# SINTETIZADOR_Y_DDS_SLAVE.net
KiCad netlist of a schematic drawn in Altium Designer
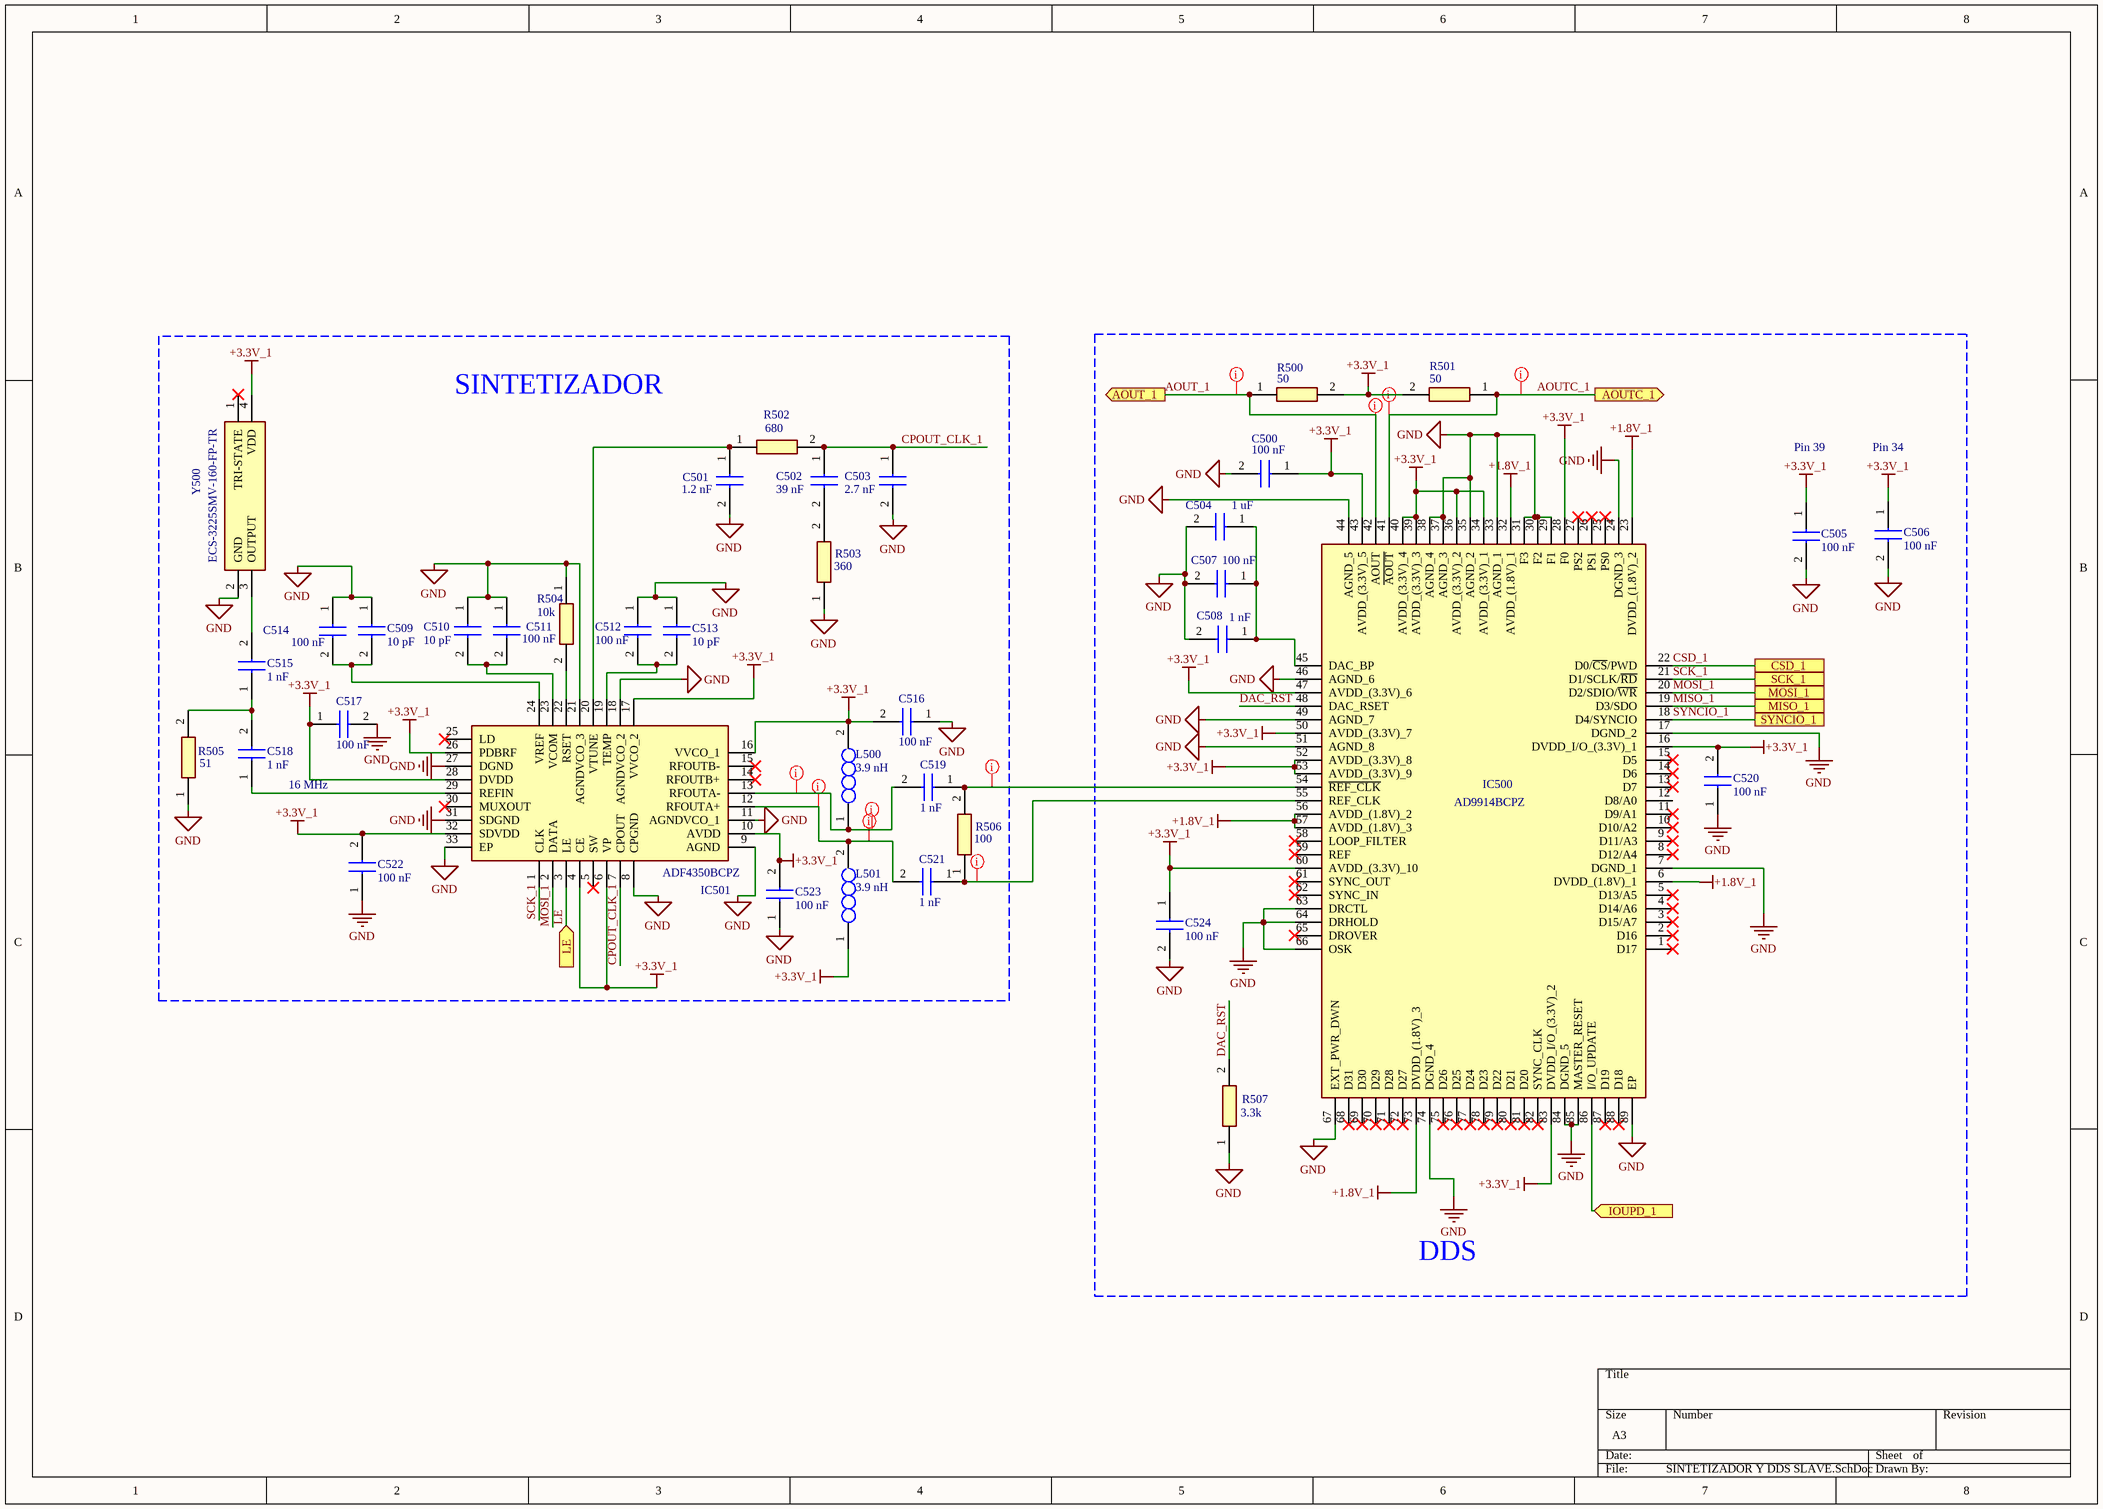
[diagram p0: SINTETIZADOR Y DDS SLAVE.SchDoc]

(export (version "E")
  (design (tool "Eeschema 10.0.6"))
  (components
    (comp (ref "C500")
      (value "100 nF")
      (footprint "SamacSys:C0603")
      (description "Capacitor")
      (fields (field (name "MANUFACTURER_PART_NUMBER") "C0603H470J5GACTU"))
      (libsource (lib "LIBRERIA_GEN_V2.0") (part "C0603H470J5GACTU"))
    )
    (comp (ref "C501")
      (value "1.2 nF")
      (footprint "SamacSys:C0603")
      (description "Capacitor")
      (fields (field (name "MANUFACTURER_PART_NUMBER") "C0603H470J5GACTU"))
      (libsource (lib "LIBRERIA_GEN_V2.0") (part "C0603H470J5GACTU"))
    )
    (comp (ref "C502")
      (value "39 nF")
      (footprint "SamacSys:C0603")
      (description "Capacitor")
      (fields (field (name "MANUFACTURER_PART_NUMBER") "C0603H470J5GACTU"))
      (libsource (lib "LIBRERIA_GEN_V2.0") (part "C0603H470J5GACTU"))
    )
    (comp (ref "C503")
      (value "2.7 nF")
      (footprint "SamacSys:C0603")
      (description "Capacitor")
      (fields (field (name "MANUFACTURER_PART_NUMBER") "C0603H470J5GACTU"))
      (libsource (lib "LIBRERIA_GEN_V2.0") (part "C0603H470J5GACTU"))
    )
    (comp (ref "C504")
      (value "1 uF")
      (footprint "SamacSys:C0603")
      (description "Capacitor")
      (fields (field (name "MANUFACTURER_PART_NUMBER") "C0603H470J5GACTU"))
      (libsource (lib "LIBRERIA_GEN_V2.0") (part "C0603H470J5GACTU"))
    )
    (comp (ref "C505")
      (value "100 nF")
      (footprint "SamacSys:C0603")
      (description "Capacitor")
      (fields (field (name "MANUFACTURER_PART_NUMBER") "C0603H470J5GACTU"))
      (libsource (lib "LIBRERIA_GEN_V2.0") (part "C0603H470J5GACTU"))
    )
    (comp (ref "C506")
      (value "100 nF")
      (footprint "SamacSys:C0603")
      (description "Capacitor")
      (fields (field (name "MANUFACTURER_PART_NUMBER") "C0603H470J5GACTU"))
      (libsource (lib "LIBRERIA_GEN_V2.0") (part "C0603H470J5GACTU"))
    )
    (comp (ref "C507")
      (value "100 nF")
      (footprint "SamacSys:C0603")
      (description "Capacitor")
      (fields (field (name "MANUFACTURER_PART_NUMBER") "C0603H470J5GACTU"))
      (libsource (lib "LIBRERIA_GEN_V2.0") (part "C0603H470J5GACTU"))
    )
    (comp (ref "C508")
      (value "1 nF")
      (footprint "SamacSys:C0603")
      (description "Capacitor")
      (fields (field (name "MANUFACTURER_PART_NUMBER") "C0603H470J5GACTU"))
      (libsource (lib "LIBRERIA_GEN_V2.0") (part "C0603H470J5GACTU"))
    )
    (comp (ref "C509")
      (value "10 pF")
      (footprint "SamacSys:C0603")
      (description "Capacitor")
      (fields (field (name "MANUFACTURER_PART_NUMBER") "C0603H470J5GACTU"))
      (libsource (lib "LIBRERIA_GEN_V2.0") (part "C0603H470J5GACTU"))
    )
    (comp (ref "C510")
      (value "10 pF")
      (footprint "SamacSys:C0603")
      (description "Capacitor")
      (fields (field (name "MANUFACTURER_PART_NUMBER") "C0603H470J5GACTU"))
      (libsource (lib "LIBRERIA_GEN_V2.0") (part "C0603H470J5GACTU"))
    )
    (comp (ref "C511")
      (value "100 nF")
      (footprint "SamacSys:C0603")
      (description "Capacitor")
      (fields (field (name "MANUFACTURER_PART_NUMBER") "C0603H470J5GACTU"))
      (libsource (lib "LIBRERIA_GEN_V2.0") (part "C0603H470J5GACTU"))
    )
    (comp (ref "C512")
      (value "100 nF")
      (footprint "SamacSys:C0603")
      (description "Capacitor")
      (fields (field (name "MANUFACTURER_PART_NUMBER") "C0603H470J5GACTU"))
      (libsource (lib "LIBRERIA_GEN_V2.0") (part "C0603H470J5GACTU"))
    )
    (comp (ref "C513")
      (value "10 pF")
      (footprint "SamacSys:C0603")
      (description "Capacitor")
      (fields (field (name "MANUFACTURER_PART_NUMBER") "C0603H470J5GACTU"))
      (libsource (lib "LIBRERIA_GEN_V2.0") (part "C0603H470J5GACTU"))
    )
    (comp (ref "C514")
      (value "100 nF")
      (footprint "SamacSys:C0603")
      (description "Capacitor")
      (fields (field (name "MANUFACTURER_PART_NUMBER") "C0603H470J5GACTU"))
      (libsource (lib "LIBRERIA_GEN_V2.0") (part "C0603H470J5GACTU"))
    )
    (comp (ref "C515")
      (value "1 nF")
      (footprint "SamacSys:C0603")
      (description "Capacitor")
      (fields (field (name "MANUFACTURER_PART_NUMBER") "C0603H470J5GACTU"))
      (libsource (lib "LIBRERIA_GEN_V2.0") (part "C0603H470J5GACTU"))
    )
    (comp (ref "C516")
      (value "100 nF")
      (footprint "SamacSys:C0603")
      (description "Capacitor")
      (fields (field (name "MANUFACTURER_PART_NUMBER") "C0603H470J5GACTU"))
      (libsource (lib "LIBRERIA_GEN_V2.0") (part "C0603H470J5GACTU"))
    )
    (comp (ref "C517")
      (value "100 nF")
      (footprint "SamacSys:C0603")
      (description "Capacitor")
      (fields (field (name "MANUFACTURER_PART_NUMBER") "C0603H470J5GACTU"))
      (libsource (lib "LIBRERIA_GEN_V2.0") (part "C0603H470J5GACTU"))
    )
    (comp (ref "C518")
      (value "1 nF")
      (footprint "SamacSys:C0603")
      (description "Capacitor")
      (fields (field (name "MANUFACTURER_PART_NUMBER") "C0603H470J5GACTU"))
      (libsource (lib "LIBRERIA_GEN_V2.0") (part "C0603H470J5GACTU"))
    )
    (comp (ref "C519")
      (value "1 nF")
      (footprint "SamacSys:C0603")
      (description "Capacitor")
      (fields (field (name "MANUFACTURER_PART_NUMBER") "C0603H470J5GACTU"))
      (libsource (lib "LIBRERIA_GEN_V2.0") (part "C0603H470J5GACTU"))
    )
    (comp (ref "C520")
      (value "100 nF")
      (footprint "SamacSys:C0603")
      (description "Capacitor")
      (fields (field (name "MANUFACTURER_PART_NUMBER") "C0603H470J5GACTU"))
      (libsource (lib "LIBRERIA_GEN_V2.0") (part "C0603H470J5GACTU"))
    )
    (comp (ref "C521")
      (value "1 nF")
      (footprint "SamacSys:C0603")
      (description "Capacitor")
      (fields (field (name "MANUFACTURER_PART_NUMBER") "C0603H470J5GACTU"))
      (libsource (lib "LIBRERIA_GEN_V2.0") (part "C0603H470J5GACTU"))
    )
    (comp (ref "C522")
      (value "100 nF")
      (footprint "SamacSys:C0603")
      (description "Capacitor")
      (fields (field (name "MANUFACTURER_PART_NUMBER") "C0603H470J5GACTU"))
      (libsource (lib "LIBRERIA_GEN_V2.0") (part "C0603H470J5GACTU"))
    )
    (comp (ref "C523")
      (value "100 nF")
      (footprint "SamacSys:C0603")
      (description "Capacitor")
      (fields (field (name "MANUFACTURER_PART_NUMBER") "C0603H470J5GACTU"))
      (libsource (lib "LIBRERIA_GEN_V2.0") (part "C0603H470J5GACTU"))
    )
    (comp (ref "C524")
      (value "100 nF")
      (footprint "SamacSys:C0603")
      (description "Capacitor")
      (fields (field (name "MANUFACTURER_PART_NUMBER") "C0603H470J5GACTU"))
      (libsource (lib "LIBRERIA_GEN_V2.0") (part "C0603H470J5GACTU"))
    )
    (comp (ref "IC500")
      (value "AD9914BCPZ")
      (footprint "SamacSys:QFN50P1200X1200X90-89N-D")
      (description "Integrated Circuit")
      (fields (field (name "MOUSER PART NUMBER") "584-AD9914BCPZ"))
      (libsource (lib "LIBRERIA_GEN_V2.0") (part "AD9914BCPZ"))
    )
    (comp (ref "IC501")
      (value "ADF4350BCPZ")
      (footprint "SamacSys:QFN50P500X500X100-33N")
      (description "Integrated Circuit")
      (fields (field (name "MOUSER PART NUMBER") "584-ADF4350BCPZ"))
      (libsource (lib "LIBRERIA_GEN_V2.0") (part "ADF4350BCPZ"))
    )
    (comp (ref "L500")
      (value "3.9 nH")
      (footprint "SamacSys:INDC1608X95N")
      (description "Inductor")
      (fields
        (field (name "MANUFACTURER_PART_NUMBER") "AIML-0603-100K-T")
        (field (name "MOUSER PART NUMBER") "815-AIML-0603-100KT")
      )
      (libsource (lib "*") (part "AIML-0603-100K-T"))
    )
    (comp (ref "L501")
      (value "3.9 nH")
      (footprint "SamacSys:INDC1608X95N")
      (description "Inductor")
      (fields
        (field (name "MANUFACTURER_PART_NUMBER") "AIML-0603-100K-T")
        (field (name "MOUSER PART NUMBER") "815-AIML-0603-100KT")
      )
      (libsource (lib "*") (part "AIML-0603-100K-T"))
    )
    (comp (ref "R500")
      (value "50")
      (footprint "SamacSys:RESC1608X55N")
      (description "Resistor")
      (fields
        (field (name "MANUFACTURER_PART_NUMBER") "CR0603-FX-1431ELF")
        (field (name "MOUSER PART NUMBER") "652-CR0603FX-1431ELF")
      )
      (libsource (lib "") (part "CR0603-FX-1431ELF_1"))
    )
    (comp (ref "R501")
      (value "50")
      (footprint "SamacSys:RESC1608X55N")
      (description "Resistor")
      (fields
        (field (name "MANUFACTURER_PART_NUMBER") "CR0603-FX-1431ELF")
        (field (name "MOUSER PART NUMBER") "652-CR0603FX-1431ELF")
      )
      (libsource (lib "") (part "CR0603-FX-1431ELF_3"))
    )
    (comp (ref "R502")
      (value "680")
      (footprint "SamacSys:RESC1608X55N")
      (description "Resistor")
      (fields
        (field (name "MANUFACTURER_PART_NUMBER") "CR0603-FX-1431ELF")
        (field (name "MOUSER PART NUMBER") "652-CR0603FX-1431ELF")
      )
      (libsource (lib "") (part "CR0603-FX-1431ELF_1"))
    )
    (comp (ref "R503")
      (value "360")
      (footprint "SamacSys:RESC1608X55N")
      (description "Resistor")
      (fields
        (field (name "MANUFACTURER_PART_NUMBER") "CR0603-FX-1431ELF")
        (field (name "MOUSER PART NUMBER") "652-CR0603FX-1431ELF")
      )
      (libsource (lib "LIBRERIA_GEN_V2.0") (part "CR0603-FX-1431ELF"))
    )
    (comp (ref "R504")
      (value "10k")
      (footprint "SamacSys:RESC1608X55N")
      (description "Resistor")
      (fields
        (field (name "MANUFACTURER_PART_NUMBER") "CR0603-FX-1431ELF")
        (field (name "MOUSER PART NUMBER") "652-CR0603FX-1431ELF")
      )
      (libsource (lib "") (part "CR0603-FX-1431ELF_2"))
    )
    (comp (ref "R505")
      (value "51")
      (footprint "SamacSys:RESC1608X55N")
      (description "Resistor")
      (fields
        (field (name "MANUFACTURER_PART_NUMBER") "CR0603-FX-1431ELF")
        (field (name "MOUSER PART NUMBER") "652-CR0603FX-1431ELF")
      )
      (libsource (lib "LIBRERIA_GEN_V2.0") (part "CR0603-FX-1431ELF"))
    )
    (comp (ref "R506")
      (value "100")
      (footprint "SamacSys:RESC1608X55N")
      (description "Resistor")
      (fields
        (field (name "MANUFACTURER_PART_NUMBER") "CR0603-FX-1431ELF")
        (field (name "MOUSER PART NUMBER") "652-CR0603FX-1431ELF")
      )
      (libsource (lib "LIBRERIA_GEN_V2.0") (part "CR0603-FX-1431ELF"))
    )
    (comp (ref "R507")
      (value "3.3k")
      (footprint "SamacSys:RESC1608X55N")
      (description "Resistor")
      (fields
        (field (name "MANUFACTURER_PART_NUMBER") "CR0603-FX-1431ELF")
        (field (name "MOUSER PART NUMBER") "652-CR0603FX-1431ELF")
      )
      (libsource (lib "LIBRERIA_GEN_V2.0") (part "CR0603-FX-1431ELF"))
    )
    (comp (ref "Y500")
      (value "ECS-3225SMV-160-FP-TR")
      (footprint "SamacSys:ECS3225SMV160FPTR")
      (description "Crystal or Oscillator")
      (fields (field (name "MOUSER PART NUMBER") "520-3225SMV-160-FPT"))
      (libsource (lib "LIBRERIA_GEN_V2.0") (part "ECS-3225SMV-160-FP-TR"))
    )
  )
  (nets
    (net (code "1") (name "+1.8V_1") (class "Default")
      (node (ref "IC500") (pin "23") (pinfunction "DVDD_(1.8V)_2_23") (pintype "passive"))
      (node (ref "IC500") (pin "32") (pinfunction "AVDD_(1.8V)_1_32") (pintype "passive"))
      (node (ref "IC500") (pin "56") (pinfunction "AVDD_(1.8V)_2_56") (pintype "passive"))
      (node (ref "IC500") (pin "57") (pinfunction "AVDD_(1.8V)_3_57") (pintype "passive"))
      (node (ref "IC500") (pin "6") (pinfunction "DVDD_(1.8V)_1_6") (pintype "passive"))
      (node (ref "IC500") (pin "73") (pinfunction "DVDD_(1.8V)_3_73") (pintype "passive"))
    )
    (net (code "2") (name "+3.3V_1") (class "Default")
      (node (ref "C500") (pin "1") (pinfunction "1_1") (pintype "passive"))
      (node (ref "C505") (pin "1") (pinfunction "1_1") (pintype "passive"))
      (node (ref "C506") (pin "1") (pinfunction "1_1") (pintype "passive"))
      (node (ref "C516") (pin "2") (pinfunction "2_2") (pintype "passive"))
      (node (ref "C517") (pin "1") (pinfunction "1_1") (pintype "passive"))
      (node (ref "C520") (pin "2") (pinfunction "2_2") (pintype "passive"))
      (node (ref "C522") (pin "2") (pinfunction "2_2") (pintype "passive"))
      (node (ref "C523") (pin "2") (pinfunction "2_2") (pintype "passive"))
      (node (ref "C524") (pin "1") (pinfunction "1_1") (pintype "passive"))
      (node (ref "IC500") (pin "16") (pinfunction "DVDD_I/O_(3.3V)_1_16") (pintype "passive"))
      (node (ref "IC500") (pin "28") (pinfunction "F0_28") (pintype "passive"))
      (node (ref "IC500") (pin "34") (pinfunction "AVDD_(3.3V)_1_34") (pintype "passive"))
      (node (ref "IC500") (pin "36") (pinfunction "AVDD_(3.3V)_2_36") (pintype "passive"))
      (node (ref "IC500") (pin "39") (pinfunction "AVDD_(3.3V)_3_39") (pintype "passive"))
      (node (ref "IC500") (pin "40") (pinfunction "AVDD_(3.3V)_4_40") (pintype "passive"))
      (node (ref "IC500") (pin "43") (pinfunction "AVDD_(3.3V)_5_43") (pintype "passive"))
      (node (ref "IC500") (pin "47") (pinfunction "AVDD_(3.3V)_6_47") (pintype "passive"))
      (node (ref "IC500") (pin "50") (pinfunction "AVDD_(3.3V)_7_50") (pintype "passive"))
      (node (ref "IC500") (pin "52") (pinfunction "AVDD_(3.3V)_8_52") (pintype "passive"))
      (node (ref "IC500") (pin "53") (pinfunction "AVDD_(3.3V)_9_53") (pintype "passive"))
      (node (ref "IC500") (pin "60") (pinfunction "AVDD_(3.3V)_10_60") (pintype "passive"))
      (node (ref "IC500") (pin "83") (pinfunction "DVDD_I/O_(3.3V)_2_83") (pintype "passive"))
      (node (ref "IC501") (pin "10") (pinfunction "AVDD_10") (pintype "passive"))
      (node (ref "IC501") (pin "16") (pinfunction "VVCO_1_16") (pintype "passive"))
      (node (ref "IC501") (pin "17") (pinfunction "VVCO_2_17") (pintype "passive"))
      (node (ref "IC501") (pin "26") (pinfunction "PDBRF_26") (pintype "passive"))
      (node (ref "IC501") (pin "28") (pinfunction "DVDD_28") (pintype "passive"))
      (node (ref "IC501") (pin "32") (pinfunction "SDVDD_32") (pintype "passive"))
      (node (ref "IC501") (pin "4") (pinfunction "CE_4") (pintype "passive"))
      (node (ref "IC501") (pin "6") (pinfunction "VP_6") (pintype "passive"))
      (node (ref "L500") (pin "2") (pinfunction "2_2") (pintype "passive"))
      (node (ref "L501") (pin "1") (pinfunction "1_1") (pintype "passive"))
      (node (ref "R500") (pin "2") (pinfunction "2_2") (pintype "passive"))
      (node (ref "R501") (pin "2") (pinfunction "2_2") (pintype "passive"))
      (node (ref "Y500") (pin "4") (pinfunction "VDD_4") (pintype "passive"))
    )
    (net (code "3") (name "/AOUTC_1") (class "Default")
      (node (ref "IC500") (pin "41") (pinfunction "~{AOUT}_41") (pintype "passive"))
      (node (ref "R501") (pin "1") (pinfunction "1_1") (pintype "passive"))
    )
    (net (code "4") (name "/AOUT_1") (class "Default")
      (node (ref "IC500") (pin "42") (pinfunction "AOUT_42") (pintype "passive"))
      (node (ref "R500") (pin "1") (pinfunction "1_1") (pintype "passive"))
    )
    (net (code "5") (name "/CPOUT_CLK_1") (class "Default")
      (node (ref "C502") (pin "1") (pinfunction "1_1") (pintype "passive"))
      (node (ref "C503") (pin "1") (pinfunction "1_1") (pintype "passive"))
      (node (ref "IC501") (pin "7") (pinfunction "CPOUT_7") (pintype "passive"))
      (node (ref "R502") (pin "2") (pinfunction "2_2") (pintype "passive"))
    )
    (net (code "6") (name "/CSD_1") (class "Default")
      (node (ref "IC500") (pin "22") (pinfunction "D0/~{CS}/PWD_22") (pintype "passive"))
    )
    (net (code "7") (name "/DAC_RST") (class "Default")
      (node (ref "IC500") (pin "48") (pinfunction "DAC_RSET_48") (pintype "passive"))
      (node (ref "R507") (pin "2") (pinfunction "2_2") (pintype "passive"))
    )
    (net (code "8") (name "/IOUPD_1") (class "Default")
      (node (ref "IC500") (pin "86") (pinfunction "I/O_UPDATE_86") (pintype "passive"))
    )
    (net (code "9") (name "/LE") (class "Default")
      (node (ref "IC501") (pin "3") (pinfunction "LE_3") (pintype "passive"))
    )
    (net (code "10") (name "/MISO_1") (class "Default")
      (node (ref "IC500") (pin "19") (pinfunction "D3/SDO_19") (pintype "passive"))
    )
    (net (code "11") (name "/MOSI_1") (class "Default")
      (node (ref "IC500") (pin "20") (pinfunction "D2/SDIO/~{WR}_20") (pintype "passive"))
      (node (ref "IC501") (pin "2") (pinfunction "DATA_2") (pintype "passive"))
    )
    (net (code "12") (name "/SCK_1") (class "Default")
      (node (ref "IC500") (pin "21") (pinfunction "D1/SCLK/~{RD}_21") (pintype "passive"))
      (node (ref "IC501") (pin "1") (pinfunction "CLK_1") (pintype "passive"))
    )
    (net (code "13") (name "/SYNCIO_1") (class "Default")
      (node (ref "IC500") (pin "18") (pinfunction "D4/SYNCIO_18") (pintype "passive"))
    )
    (net (code "14") (name "GND") (class "Default")
      (node (ref "C500") (pin "2") (pinfunction "2_2") (pintype "passive"))
      (node (ref "C501") (pin "2") (pinfunction "2_2") (pintype "passive"))
      (node (ref "C503") (pin "2") (pinfunction "2_2") (pintype "passive"))
      (node (ref "C504") (pin "2") (pinfunction "2_2") (pintype "passive"))
      (node (ref "C505") (pin "2") (pinfunction "2_2") (pintype "passive"))
      (node (ref "C506") (pin "2") (pinfunction "2_2") (pintype "passive"))
      (node (ref "C507") (pin "2") (pinfunction "2_2") (pintype "passive"))
      (node (ref "C508") (pin "2") (pinfunction "2_2") (pintype "passive"))
      (node (ref "C509") (pin "1") (pinfunction "1_1") (pintype "passive"))
      (node (ref "C510") (pin "1") (pinfunction "1_1") (pintype "passive"))
      (node (ref "C511") (pin "1") (pinfunction "1_1") (pintype "passive"))
      (node (ref "C512") (pin "1") (pinfunction "1_1") (pintype "passive"))
      (node (ref "C513") (pin "1") (pinfunction "1_1") (pintype "passive"))
      (node (ref "C514") (pin "1") (pinfunction "1_1") (pintype "passive"))
      (node (ref "C516") (pin "1") (pinfunction "1_1") (pintype "passive"))
      (node (ref "C517") (pin "2") (pinfunction "2_2") (pintype "passive"))
      (node (ref "C520") (pin "1") (pinfunction "1_1") (pintype "passive"))
      (node (ref "C522") (pin "1") (pinfunction "1_1") (pintype "passive"))
      (node (ref "C523") (pin "1") (pinfunction "1_1") (pintype "passive"))
      (node (ref "C524") (pin "2") (pinfunction "2_2") (pintype "passive"))
      (node (ref "IC500") (pin "17") (pinfunction "DGND_2_17") (pintype "passive"))
      (node (ref "IC500") (pin "24") (pinfunction "DGND_3_24") (pintype "passive"))
      (node (ref "IC500") (pin "29") (pinfunction "F1_29") (pintype "passive"))
      (node (ref "IC500") (pin "30") (pinfunction "F2_30") (pintype "passive"))
      (node (ref "IC500") (pin "31") (pinfunction "F3_31") (pintype "passive"))
      (node (ref "IC500") (pin "33") (pinfunction "AGND_1_33") (pintype "passive"))
      (node (ref "IC500") (pin "35") (pinfunction "AGND_2_35") (pintype "passive"))
      (node (ref "IC500") (pin "37") (pinfunction "AGND_3_37") (pintype "passive"))
      (node (ref "IC500") (pin "38") (pinfunction "AGND_4_38") (pintype "passive"))
      (node (ref "IC500") (pin "44") (pinfunction "AGND_5_44") (pintype "passive"))
      (node (ref "IC500") (pin "46") (pinfunction "AGND_6_46") (pintype "passive"))
      (node (ref "IC500") (pin "49") (pinfunction "AGND_7_49") (pintype "passive"))
      (node (ref "IC500") (pin "51") (pinfunction "AGND_8_51") (pintype "passive"))
      (node (ref "IC500") (pin "63") (pinfunction "DRCTL_63") (pintype "passive"))
      (node (ref "IC500") (pin "64") (pinfunction "DRHOLD_64") (pintype "passive"))
      (node (ref "IC500") (pin "66") (pinfunction "OSK_66") (pintype "passive"))
      (node (ref "IC500") (pin "67") (pinfunction "EXT_PWR_DWN_67") (pintype "passive"))
      (node (ref "IC500") (pin "7") (pinfunction "DGND_1_7") (pintype "passive"))
      (node (ref "IC500") (pin "74") (pinfunction "DGND_4_74") (pintype "passive"))
      (node (ref "IC500") (pin "84") (pinfunction "DGND_5_84") (pintype "passive"))
      (node (ref "IC500") (pin "85") (pinfunction "MASTER_RESET_85") (pintype "passive"))
      (node (ref "IC500") (pin "89") (pinfunction "EP_89") (pintype "passive"))
      (node (ref "IC501") (pin "11") (pinfunction "AGNDVCO_1_11") (pintype "passive"))
      (node (ref "IC501") (pin "18") (pinfunction "AGNDVCO_2_18") (pintype "passive"))
      (node (ref "IC501") (pin "21") (pinfunction "AGNDVCO_3_21") (pintype "passive"))
      (node (ref "IC501") (pin "27") (pinfunction "DGND_27") (pintype "passive"))
      (node (ref "IC501") (pin "31") (pinfunction "SDGND_31") (pintype "passive"))
      (node (ref "IC501") (pin "33") (pinfunction "EP_33") (pintype "passive"))
      (node (ref "IC501") (pin "8") (pinfunction "CPGND_8") (pintype "passive"))
      (node (ref "IC501") (pin "9") (pinfunction "AGND_9") (pintype "passive"))
      (node (ref "R503") (pin "1") (pinfunction "1_1") (pintype "passive"))
      (node (ref "R504") (pin "1") (pinfunction "1_1") (pintype "passive"))
      (node (ref "R505") (pin "1") (pinfunction "1_1") (pintype "passive"))
      (node (ref "R507") (pin "1") (pinfunction "1_1") (pintype "passive"))
      (node (ref "Y500") (pin "2") (pinfunction "GND_2") (pintype "passive"))
    )
    (net (code "15") (name "Net-(C502-Pad2)") (class "Default")
      (node (ref "C502") (pin "2") (pinfunction "2_2") (pintype "passive"))
      (node (ref "R503") (pin "2") (pinfunction "2_2") (pintype "passive"))
    )
    (net (code "16") (name "Net-(C515-Pad1)") (class "Default")
      (node (ref "C515") (pin "1") (pinfunction "1_1") (pintype "passive"))
      (node (ref "C518") (pin "2") (pinfunction "2_2") (pintype "passive"))
      (node (ref "R505") (pin "2") (pinfunction "2_2") (pintype "passive"))
    )
    (net (code "17") (name "Net-(IC500-DAC_BP)") (class "Default")
      (node (ref "C504") (pin "1") (pinfunction "1_1") (pintype "passive"))
      (node (ref "C507") (pin "1") (pinfunction "1_1") (pintype "passive"))
      (node (ref "C508") (pin "1") (pinfunction "1_1") (pintype "passive"))
      (node (ref "IC500") (pin "45") (pinfunction "DAC_BP_45") (pintype "passive"))
    )
    (net (code "18") (name "Net-(IC500-REF_CLK)") (class "Default")
      (node (ref "C521") (pin "1") (pinfunction "1_1") (pintype "passive"))
      (node (ref "IC500") (pin "55") (pinfunction "REF_CLK_55") (pintype "passive"))
      (node (ref "R506") (pin "1") (pinfunction "1_1") (pintype "passive"))
    )
    (net (code "19") (name "Net-(IC500-~{REF_CLK})") (class "Default")
      (node (ref "C519") (pin "1") (pinfunction "1_1") (pintype "passive"))
      (node (ref "IC500") (pin "54") (pinfunction "~{REF_CLK}_54") (pintype "passive"))
      (node (ref "R506") (pin "2") (pinfunction "2_2") (pintype "passive"))
    )
    (net (code "20") (name "Net-(IC501-REFIN)") (class "Default")
      (node (ref "C518") (pin "1") (pinfunction "1_1") (pintype "passive"))
      (node (ref "IC501") (pin "29") (pinfunction "REFIN_29") (pintype "passive"))
    )
    (net (code "21") (name "Net-(IC501-RFOUTA+)") (class "Default")
      (node (ref "C521") (pin "2") (pinfunction "2_2") (pintype "passive"))
      (node (ref "IC501") (pin "12") (pinfunction "RFOUTA+_12") (pintype "passive"))
      (node (ref "L501") (pin "2") (pinfunction "2_2") (pintype "passive"))
    )
    (net (code "22") (name "Net-(IC501-RFOUTA-)") (class "Default")
      (node (ref "C519") (pin "2") (pinfunction "2_2") (pintype "passive"))
      (node (ref "IC501") (pin "13") (pinfunction "RFOUTA-_13") (pintype "passive"))
      (node (ref "L500") (pin "1") (pinfunction "1_1") (pintype "passive"))
    )
    (net (code "23") (name "Net-(IC501-RSET)") (class "Default")
      (node (ref "IC501") (pin "22") (pinfunction "RSET_22") (pintype "passive"))
      (node (ref "R504") (pin "2") (pinfunction "2_2") (pintype "passive"))
    )
    (net (code "24") (name "Net-(IC501-TEMP)") (class "Default")
      (node (ref "C512") (pin "2") (pinfunction "2_2") (pintype "passive"))
      (node (ref "C513") (pin "2") (pinfunction "2_2") (pintype "passive"))
      (node (ref "IC501") (pin "19") (pinfunction "TEMP_19") (pintype "passive"))
    )
    (net (code "25") (name "Net-(IC501-VCOM)") (class "Default")
      (node (ref "C510") (pin "2") (pinfunction "2_2") (pintype "passive"))
      (node (ref "C511") (pin "2") (pinfunction "2_2") (pintype "passive"))
      (node (ref "IC501") (pin "23") (pinfunction "VCOM_23") (pintype "passive"))
    )
    (net (code "26") (name "Net-(IC501-VREF)") (class "Default")
      (node (ref "C509") (pin "2") (pinfunction "2_2") (pintype "passive"))
      (node (ref "C514") (pin "2") (pinfunction "2_2") (pintype "passive"))
      (node (ref "IC501") (pin "24") (pinfunction "VREF_24") (pintype "passive"))
    )
    (net (code "27") (name "Net-(IC501-VTUNE)") (class "Default")
      (node (ref "C501") (pin "1") (pinfunction "1_1") (pintype "passive"))
      (node (ref "IC501") (pin "20") (pinfunction "VTUNE_20") (pintype "passive"))
      (node (ref "R502") (pin "1") (pinfunction "1_1") (pintype "passive"))
    )
    (net (code "28") (name "Net-(Y500-OUTPUT)") (class "Default")
      (node (ref "C515") (pin "2") (pinfunction "2_2") (pintype "passive"))
      (node (ref "Y500") (pin "3") (pinfunction "OUTPUT_3") (pintype "passive"))
    )
    (net (code "29") (name "unconnected-(IC500-D5-Pad15)") (class "Default")
      (node (ref "IC500") (pin "15") (pinfunction "D5_15") (pintype "passive+no_connect"))
    )
    (net (code "30") (name "unconnected-(IC500-D6-Pad14)") (class "Default")
      (node (ref "IC500") (pin "14") (pinfunction "D6_14") (pintype "passive+no_connect"))
    )
    (net (code "31") (name "unconnected-(IC500-D7-Pad13)") (class "Default")
      (node (ref "IC500") (pin "13") (pinfunction "D7_13") (pintype "passive+no_connect"))
    )
    (net (code "32") (name "unconnected-(IC500-D8{slash}A0-Pad12)") (class "Default")
      (node (ref "IC500") (pin "12") (pinfunction "D8/A0_12") (pintype "passive"))
    )
    (net (code "33") (name "unconnected-(IC500-D9{slash}A1-Pad11)") (class "Default")
      (node (ref "IC500") (pin "11") (pinfunction "D9/A1_11") (pintype "passive+no_connect"))
    )
    (net (code "34") (name "unconnected-(IC500-D10{slash}A2-Pad10)") (class "Default")
      (node (ref "IC500") (pin "10") (pinfunction "D10/A2_10") (pintype "passive+no_connect"))
    )
    (net (code "35") (name "unconnected-(IC500-D11{slash}A3-Pad9)") (class "Default")
      (node (ref "IC500") (pin "9") (pinfunction "D11/A3_9") (pintype "passive+no_connect"))
    )
    (net (code "36") (name "unconnected-(IC500-D12{slash}A4-Pad8)") (class "Default")
      (node (ref "IC500") (pin "8") (pinfunction "D12/A4_8") (pintype "passive+no_connect"))
    )
    (net (code "37") (name "unconnected-(IC500-D13{slash}A5-Pad5)") (class "Default")
      (node (ref "IC500") (pin "5") (pinfunction "D13/A5_5") (pintype "passive+no_connect"))
    )
    (net (code "38") (name "unconnected-(IC500-D14{slash}A6-Pad4)") (class "Default")
      (node (ref "IC500") (pin "4") (pinfunction "D14/A6_4") (pintype "passive+no_connect"))
    )
    (net (code "39") (name "unconnected-(IC500-D15{slash}A7-Pad3)") (class "Default")
      (node (ref "IC500") (pin "3") (pinfunction "D15/A7_3") (pintype "passive+no_connect"))
    )
    (net (code "40") (name "unconnected-(IC500-D16-Pad2)") (class "Default")
      (node (ref "IC500") (pin "2") (pinfunction "D16_2") (pintype "passive+no_connect"))
    )
    (net (code "41") (name "unconnected-(IC500-D17-Pad1)") (class "Default")
      (node (ref "IC500") (pin "1") (pinfunction "D17_1") (pintype "passive+no_connect"))
    )
    (net (code "42") (name "unconnected-(IC500-D18-Pad88)") (class "Default")
      (node (ref "IC500") (pin "88") (pinfunction "D18_88") (pintype "passive+no_connect"))
    )
    (net (code "43") (name "unconnected-(IC500-D19-Pad87)") (class "Default")
      (node (ref "IC500") (pin "87") (pinfunction "D19_87") (pintype "passive+no_connect"))
    )
    (net (code "44") (name "unconnected-(IC500-D20-Pad81)") (class "Default")
      (node (ref "IC500") (pin "81") (pinfunction "D20_81") (pintype "passive+no_connect"))
    )
    (net (code "45") (name "unconnected-(IC500-D21-Pad80)") (class "Default")
      (node (ref "IC500") (pin "80") (pinfunction "D21_80") (pintype "passive+no_connect"))
    )
    (net (code "46") (name "unconnected-(IC500-D22-Pad79)") (class "Default")
      (node (ref "IC500") (pin "79") (pinfunction "D22_79") (pintype "passive+no_connect"))
    )
    (net (code "47") (name "unconnected-(IC500-D23-Pad78)") (class "Default")
      (node (ref "IC500") (pin "78") (pinfunction "D23_78") (pintype "passive+no_connect"))
    )
    (net (code "48") (name "unconnected-(IC500-D24-Pad77)") (class "Default")
      (node (ref "IC500") (pin "77") (pinfunction "D24_77") (pintype "passive+no_connect"))
    )
    (net (code "49") (name "unconnected-(IC500-D25-Pad76)") (class "Default")
      (node (ref "IC500") (pin "76") (pinfunction "D25_76") (pintype "passive+no_connect"))
    )
    (net (code "50") (name "unconnected-(IC500-D26-Pad75)") (class "Default")
      (node (ref "IC500") (pin "75") (pinfunction "D26_75") (pintype "passive+no_connect"))
    )
    (net (code "51") (name "unconnected-(IC500-D27-Pad72)") (class "Default")
      (node (ref "IC500") (pin "72") (pinfunction "D27_72") (pintype "passive+no_connect"))
    )
    (net (code "52") (name "unconnected-(IC500-D28-Pad71)") (class "Default")
      (node (ref "IC500") (pin "71") (pinfunction "D28_71") (pintype "passive+no_connect"))
    )
    (net (code "53") (name "unconnected-(IC500-D29-Pad70)") (class "Default")
      (node (ref "IC500") (pin "70") (pinfunction "D29_70") (pintype "passive+no_connect"))
    )
    (net (code "54") (name "unconnected-(IC500-D30-Pad69)") (class "Default")
      (node (ref "IC500") (pin "69") (pinfunction "D30_69") (pintype "passive+no_connect"))
    )
    (net (code "55") (name "unconnected-(IC500-D31-Pad68)") (class "Default")
      (node (ref "IC500") (pin "68") (pinfunction "D31_68") (pintype "passive+no_connect"))
    )
    (net (code "56") (name "unconnected-(IC500-DROVER-Pad65)") (class "Default")
      (node (ref "IC500") (pin "65") (pinfunction "DROVER_65") (pintype "passive+no_connect"))
    )
    (net (code "57") (name "unconnected-(IC500-LOOP_FILTER-Pad58)") (class "Default")
      (node (ref "IC500") (pin "58") (pinfunction "LOOP_FILTER_58") (pintype "passive+no_connect"))
    )
    (net (code "58") (name "unconnected-(IC500-PS0-Pad25)") (class "Default")
      (node (ref "IC500") (pin "25") (pinfunction "PS0_25") (pintype "passive+no_connect"))
    )
    (net (code "59") (name "unconnected-(IC500-PS1-Pad26)") (class "Default")
      (node (ref "IC500") (pin "26") (pinfunction "PS1_26") (pintype "passive+no_connect"))
    )
    (net (code "60") (name "unconnected-(IC500-PS2-Pad27)") (class "Default")
      (node (ref "IC500") (pin "27") (pinfunction "PS2_27") (pintype "passive+no_connect"))
    )
    (net (code "61") (name "unconnected-(IC500-REF-Pad59)") (class "Default")
      (node (ref "IC500") (pin "59") (pinfunction "REF_59") (pintype "passive+no_connect"))
    )
    (net (code "62") (name "unconnected-(IC500-SYNC_CLK-Pad82)") (class "Default")
      (node (ref "IC500") (pin "82") (pinfunction "SYNC_CLK_82") (pintype "passive+no_connect"))
    )
    (net (code "63") (name "unconnected-(IC500-SYNC_IN-Pad62)") (class "Default")
      (node (ref "IC500") (pin "62") (pinfunction "SYNC_IN_62") (pintype "passive+no_connect"))
    )
    (net (code "64") (name "unconnected-(IC500-SYNC_OUT-Pad61)") (class "Default")
      (node (ref "IC500") (pin "61") (pinfunction "SYNC_OUT_61") (pintype "passive+no_connect"))
    )
    (net (code "65") (name "unconnected-(IC501-LD-Pad25)") (class "Default")
      (node (ref "IC501") (pin "25") (pinfunction "LD_25") (pintype "passive+no_connect"))
    )
    (net (code "66") (name "unconnected-(IC501-MUXOUT-Pad30)") (class "Default")
      (node (ref "IC501") (pin "30") (pinfunction "MUXOUT_30") (pintype "passive+no_connect"))
    )
    (net (code "67") (name "unconnected-(IC501-RFOUTB+-Pad14)") (class "Default")
      (node (ref "IC501") (pin "14") (pinfunction "RFOUTB+_14") (pintype "passive+no_connect"))
    )
    (net (code "68") (name "unconnected-(IC501-RFOUTB--Pad15)") (class "Default")
      (node (ref "IC501") (pin "15") (pinfunction "RFOUTB-_15") (pintype "passive+no_connect"))
    )
    (net (code "69") (name "unconnected-(IC501-SW-Pad5)") (class "Default")
      (node (ref "IC501") (pin "5") (pinfunction "SW_5") (pintype "passive+no_connect"))
    )
    (net (code "70") (name "unconnected-(Y500-TRI-STATE-Pad1)") (class "Default")
      (node (ref "Y500") (pin "1") (pinfunction "TRI-STATE_1") (pintype "passive+no_connect"))
    )
  )
)
